# PDB_MH.net
KiCad netlist of a schematic drawn in EAGLE
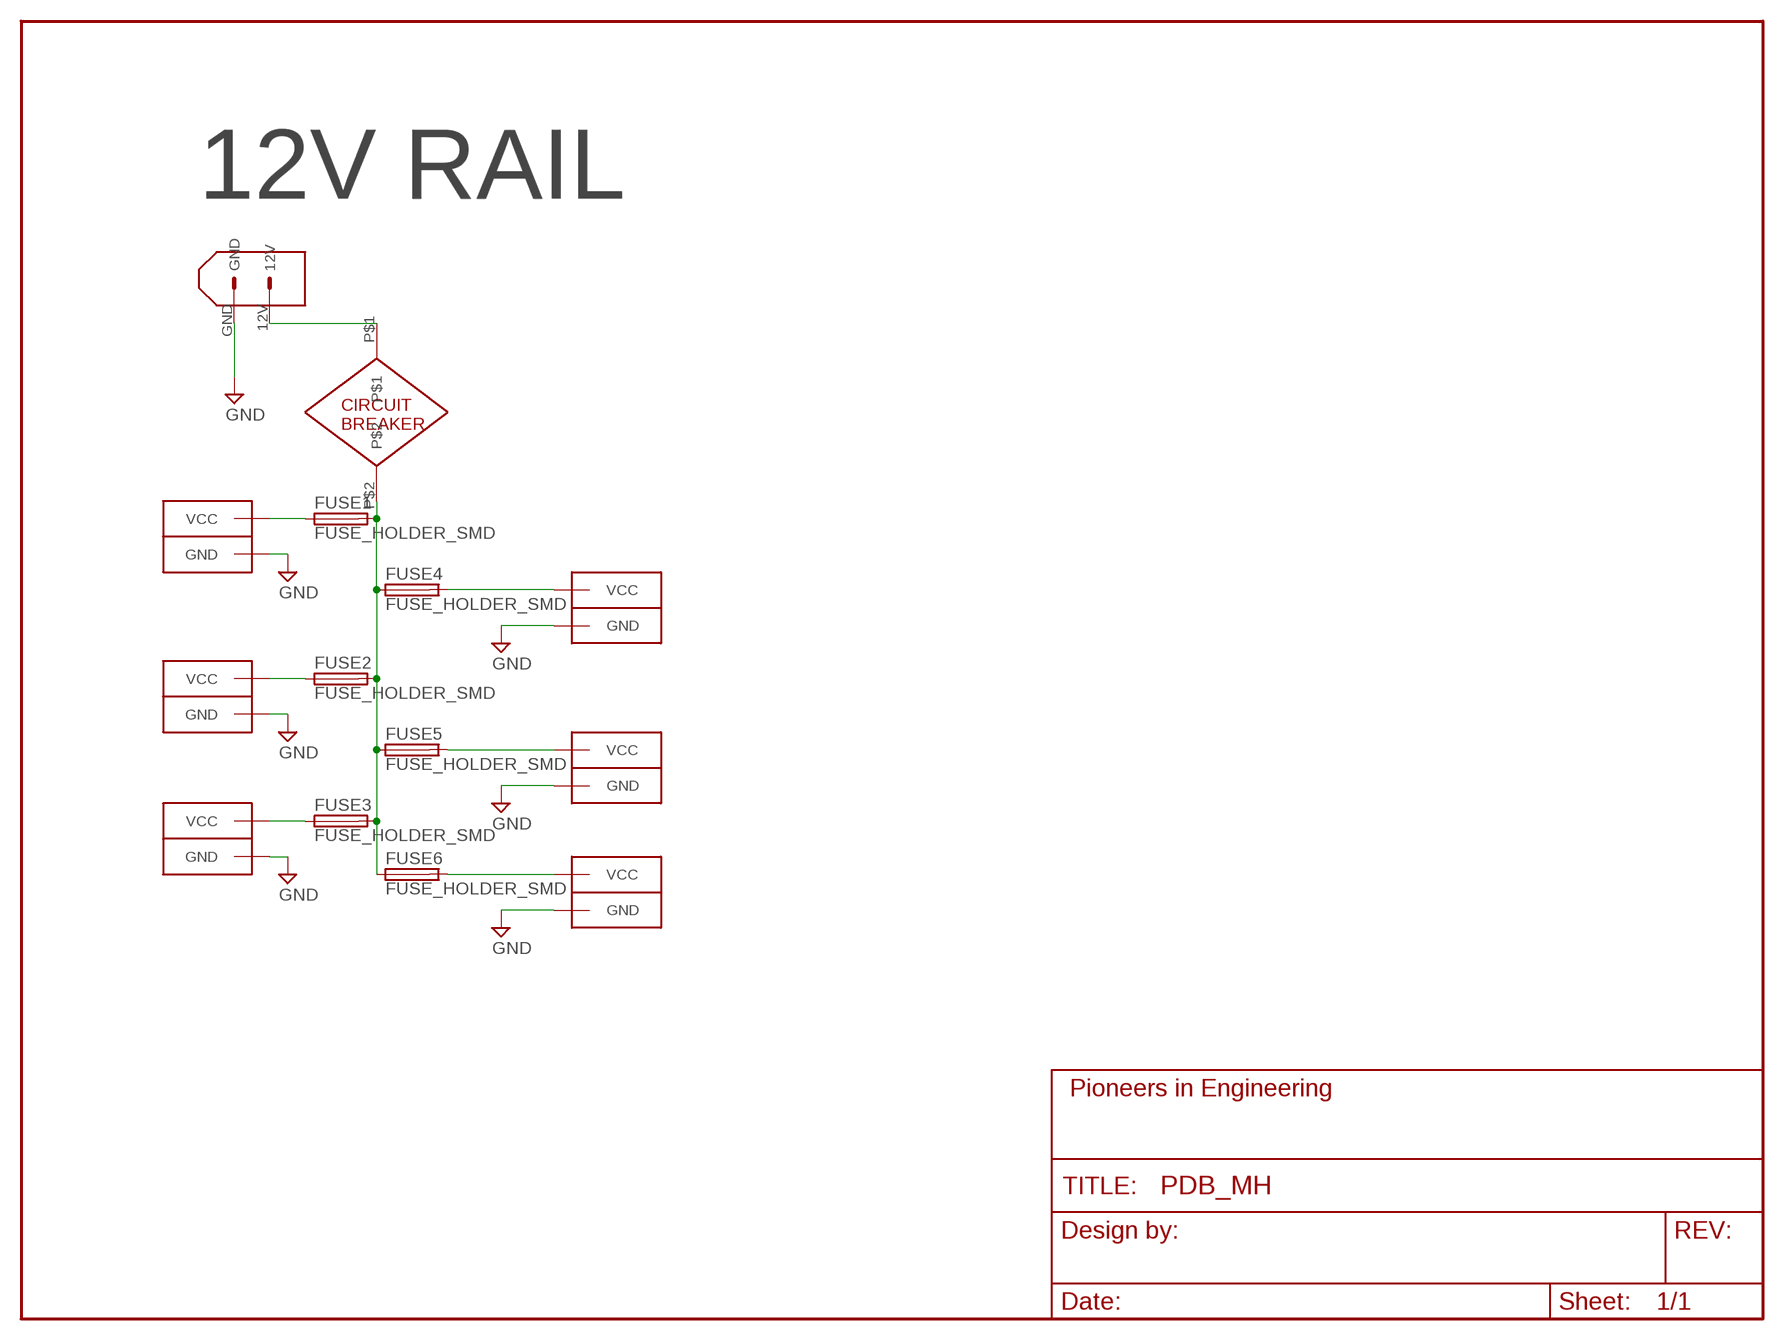
[diagram p0: schematic, sheet 1]

(export (version "E")
  (design (tool "Eeschema 10.0.6"))
  (components
    (comp (ref "CIRCUIT_BREAKER")
      (value "CIRC_BREAKER")
      (footprint "eagle-import:CIRC_BREAKER")
      (libsource (lib "eagle-import") (part "CIRC_BREAKER"))
    )
    (comp (ref "CONN1")
      (value "ANDERSONVERTICAL")
      (footprint "eagle-import:ANDERSON_VERTICAL")
      (libsource (lib "eagle-import") (part "ANDERSONVERTICAL"))
    )
    (comp (ref "CONN2")
      (value "ANDERSONVERTICAL")
      (footprint "eagle-import:ANDERSON_VERTICAL")
      (libsource (lib "eagle-import") (part "ANDERSONVERTICAL"))
    )
    (comp (ref "CONN3")
      (value "ANDERSONVERTICAL")
      (footprint "eagle-import:ANDERSON_VERTICAL")
      (libsource (lib "eagle-import") (part "ANDERSONVERTICAL"))
    )
    (comp (ref "CONN4")
      (value "ANDERSONVERTICAL")
      (footprint "eagle-import:ANDERSON_VERTICAL")
      (libsource (lib "eagle-import") (part "ANDERSONVERTICAL"))
    )
    (comp (ref "CONN5")
      (value "ANDERSONVERTICAL")
      (footprint "eagle-import:ANDERSON_VERTICAL")
      (libsource (lib "eagle-import") (part "ANDERSONVERTICAL"))
    )
    (comp (ref "CONN6")
      (value "ANDERSONVERTICAL")
      (footprint "eagle-import:ANDERSON_VERTICAL")
      (libsource (lib "eagle-import") (part "ANDERSONVERTICAL"))
    )
    (comp (ref "FUSE1")
      (value "FUSE_HOLDER_SMD")
      (footprint "eagle-import:FUSE_HOLDER_SMD")
      (libsource (lib "eagle-import") (part "FUSE_HOLDER_SMD"))
    )
    (comp (ref "FUSE2")
      (value "FUSE_HOLDER_SMD")
      (footprint "eagle-import:FUSE_HOLDER_SMD")
      (libsource (lib "eagle-import") (part "FUSE_HOLDER_SMD"))
    )
    (comp (ref "FUSE3")
      (value "FUSE_HOLDER_SMD")
      (footprint "eagle-import:FUSE_HOLDER_SMD")
      (libsource (lib "eagle-import") (part "FUSE_HOLDER_SMD"))
    )
    (comp (ref "FUSE4")
      (value "FUSE_HOLDER_SMD")
      (footprint "eagle-import:FUSE_HOLDER_SMD")
      (libsource (lib "eagle-import") (part "FUSE_HOLDER_SMD"))
    )
    (comp (ref "FUSE5")
      (value "FUSE_HOLDER_SMD")
      (footprint "eagle-import:FUSE_HOLDER_SMD")
      (libsource (lib "eagle-import") (part "FUSE_HOLDER_SMD"))
    )
    (comp (ref "FUSE6")
      (value "FUSE_HOLDER_SMD")
      (footprint "eagle-import:FUSE_HOLDER_SMD")
      (libsource (lib "eagle-import") (part "FUSE_HOLDER_SMD"))
    )
    (comp (ref "U$1")
      (value "XT60CONNECTOR")
      (footprint "eagle-import:XT60CONNECTOR")
      (fields (field (name "PARTNUMBER") "PRT-10474 "))
      (libsource (lib "eagle-import") (part "XT60CONNECTOR"))
    )
  )
  (nets
    (net (code "1") (name "GND") (class "Default")
      (node (ref "CONN1") (pin "PIN1") (pinfunction "GND_PIN1") (pintype "bidirectional"))
      (node (ref "CONN2") (pin "PIN1") (pinfunction "GND_PIN1") (pintype "bidirectional"))
      (node (ref "CONN3") (pin "PIN1") (pinfunction "GND_PIN1") (pintype "bidirectional"))
      (node (ref "CONN4") (pin "PIN1") (pinfunction "GND_PIN1") (pintype "bidirectional"))
      (node (ref "CONN5") (pin "PIN1") (pinfunction "GND_PIN1") (pintype "bidirectional"))
      (node (ref "CONN6") (pin "PIN1") (pinfunction "GND_PIN1") (pintype "bidirectional"))
      (node (ref "U$1") (pin "GND") (pinfunction "GND_GND") (pintype "bidirectional"))
    )
    (net (code "2") (name "Net-(CIRCUIT_BREAKER-PadP$1)") (class "Default")
      (node (ref "CIRCUIT_BREAKER") (pin "P$1") (pinfunction "P$1_P$1") (pintype "bidirectional"))
      (node (ref "U$1") (pin "12V") (pinfunction "12V_12V") (pintype "bidirectional"))
    )
    (net (code "3") (name "Net-(CIRCUIT_BREAKER-PadP$2)") (class "Default")
      (node (ref "CIRCUIT_BREAKER") (pin "P$2") (pinfunction "P$2_P$2") (pintype "bidirectional"))
      (node (ref "FUSE1") (pin "P$2_DOWN") (pinfunction "2_P$2_DOWN") (pintype "passive"))
      (node (ref "FUSE1") (pin "P$2_UP") (pinfunction "2_P$2_UP") (pintype "passive"))
      (node (ref "FUSE2") (pin "P$2_DOWN") (pinfunction "2_P$2_DOWN") (pintype "passive"))
      (node (ref "FUSE2") (pin "P$2_UP") (pinfunction "2_P$2_UP") (pintype "passive"))
      (node (ref "FUSE3") (pin "P$2_DOWN") (pinfunction "2_P$2_DOWN") (pintype "passive"))
      (node (ref "FUSE3") (pin "P$2_UP") (pinfunction "2_P$2_UP") (pintype "passive"))
      (node (ref "FUSE4") (pin "P$1_DOWN") (pinfunction "1_P$1_DOWN") (pintype "passive"))
      (node (ref "FUSE4") (pin "P$1_UP") (pinfunction "1_P$1_UP") (pintype "passive"))
      (node (ref "FUSE5") (pin "P$1_DOWN") (pinfunction "1_P$1_DOWN") (pintype "passive"))
      (node (ref "FUSE5") (pin "P$1_UP") (pinfunction "1_P$1_UP") (pintype "passive"))
      (node (ref "FUSE6") (pin "P$1_DOWN") (pinfunction "1_P$1_DOWN") (pintype "passive"))
      (node (ref "FUSE6") (pin "P$1_UP") (pinfunction "1_P$1_UP") (pintype "passive"))
    )
    (net (code "4") (name "Net-(CONN1-VCC)") (class "Default")
      (node (ref "CONN1") (pin "PIN2") (pinfunction "VCC_PIN2") (pintype "bidirectional"))
      (node (ref "FUSE1") (pin "P$1_DOWN") (pinfunction "1_P$1_DOWN") (pintype "passive"))
      (node (ref "FUSE1") (pin "P$1_UP") (pinfunction "1_P$1_UP") (pintype "passive"))
    )
    (net (code "5") (name "Net-(CONN2-VCC)") (class "Default")
      (node (ref "CONN2") (pin "PIN2") (pinfunction "VCC_PIN2") (pintype "bidirectional"))
      (node (ref "FUSE2") (pin "P$1_DOWN") (pinfunction "1_P$1_DOWN") (pintype "passive"))
      (node (ref "FUSE2") (pin "P$1_UP") (pinfunction "1_P$1_UP") (pintype "passive"))
    )
    (net (code "6") (name "Net-(CONN3-VCC)") (class "Default")
      (node (ref "CONN3") (pin "PIN2") (pinfunction "VCC_PIN2") (pintype "bidirectional"))
      (node (ref "FUSE3") (pin "P$1_DOWN") (pinfunction "1_P$1_DOWN") (pintype "passive"))
      (node (ref "FUSE3") (pin "P$1_UP") (pinfunction "1_P$1_UP") (pintype "passive"))
    )
    (net (code "7") (name "Net-(CONN4-VCC)") (class "Default")
      (node (ref "CONN4") (pin "PIN2") (pinfunction "VCC_PIN2") (pintype "bidirectional"))
      (node (ref "FUSE4") (pin "P$2_DOWN") (pinfunction "2_P$2_DOWN") (pintype "passive"))
      (node (ref "FUSE4") (pin "P$2_UP") (pinfunction "2_P$2_UP") (pintype "passive"))
    )
    (net (code "8") (name "Net-(CONN5-VCC)") (class "Default")
      (node (ref "CONN5") (pin "PIN2") (pinfunction "VCC_PIN2") (pintype "bidirectional"))
      (node (ref "FUSE5") (pin "P$2_DOWN") (pinfunction "2_P$2_DOWN") (pintype "passive"))
      (node (ref "FUSE5") (pin "P$2_UP") (pinfunction "2_P$2_UP") (pintype "passive"))
    )
    (net (code "9") (name "Net-(CONN6-VCC)") (class "Default")
      (node (ref "CONN6") (pin "PIN2") (pinfunction "VCC_PIN2") (pintype "bidirectional"))
      (node (ref "FUSE6") (pin "P$2_DOWN") (pinfunction "2_P$2_DOWN") (pintype "passive"))
      (node (ref "FUSE6") (pin "P$2_UP") (pinfunction "2_P$2_UP") (pintype "passive"))
    )
  )
)
